# High-Level_PCB_v3_0.net
KiCad netlist of a schematic drawn in EAGLE
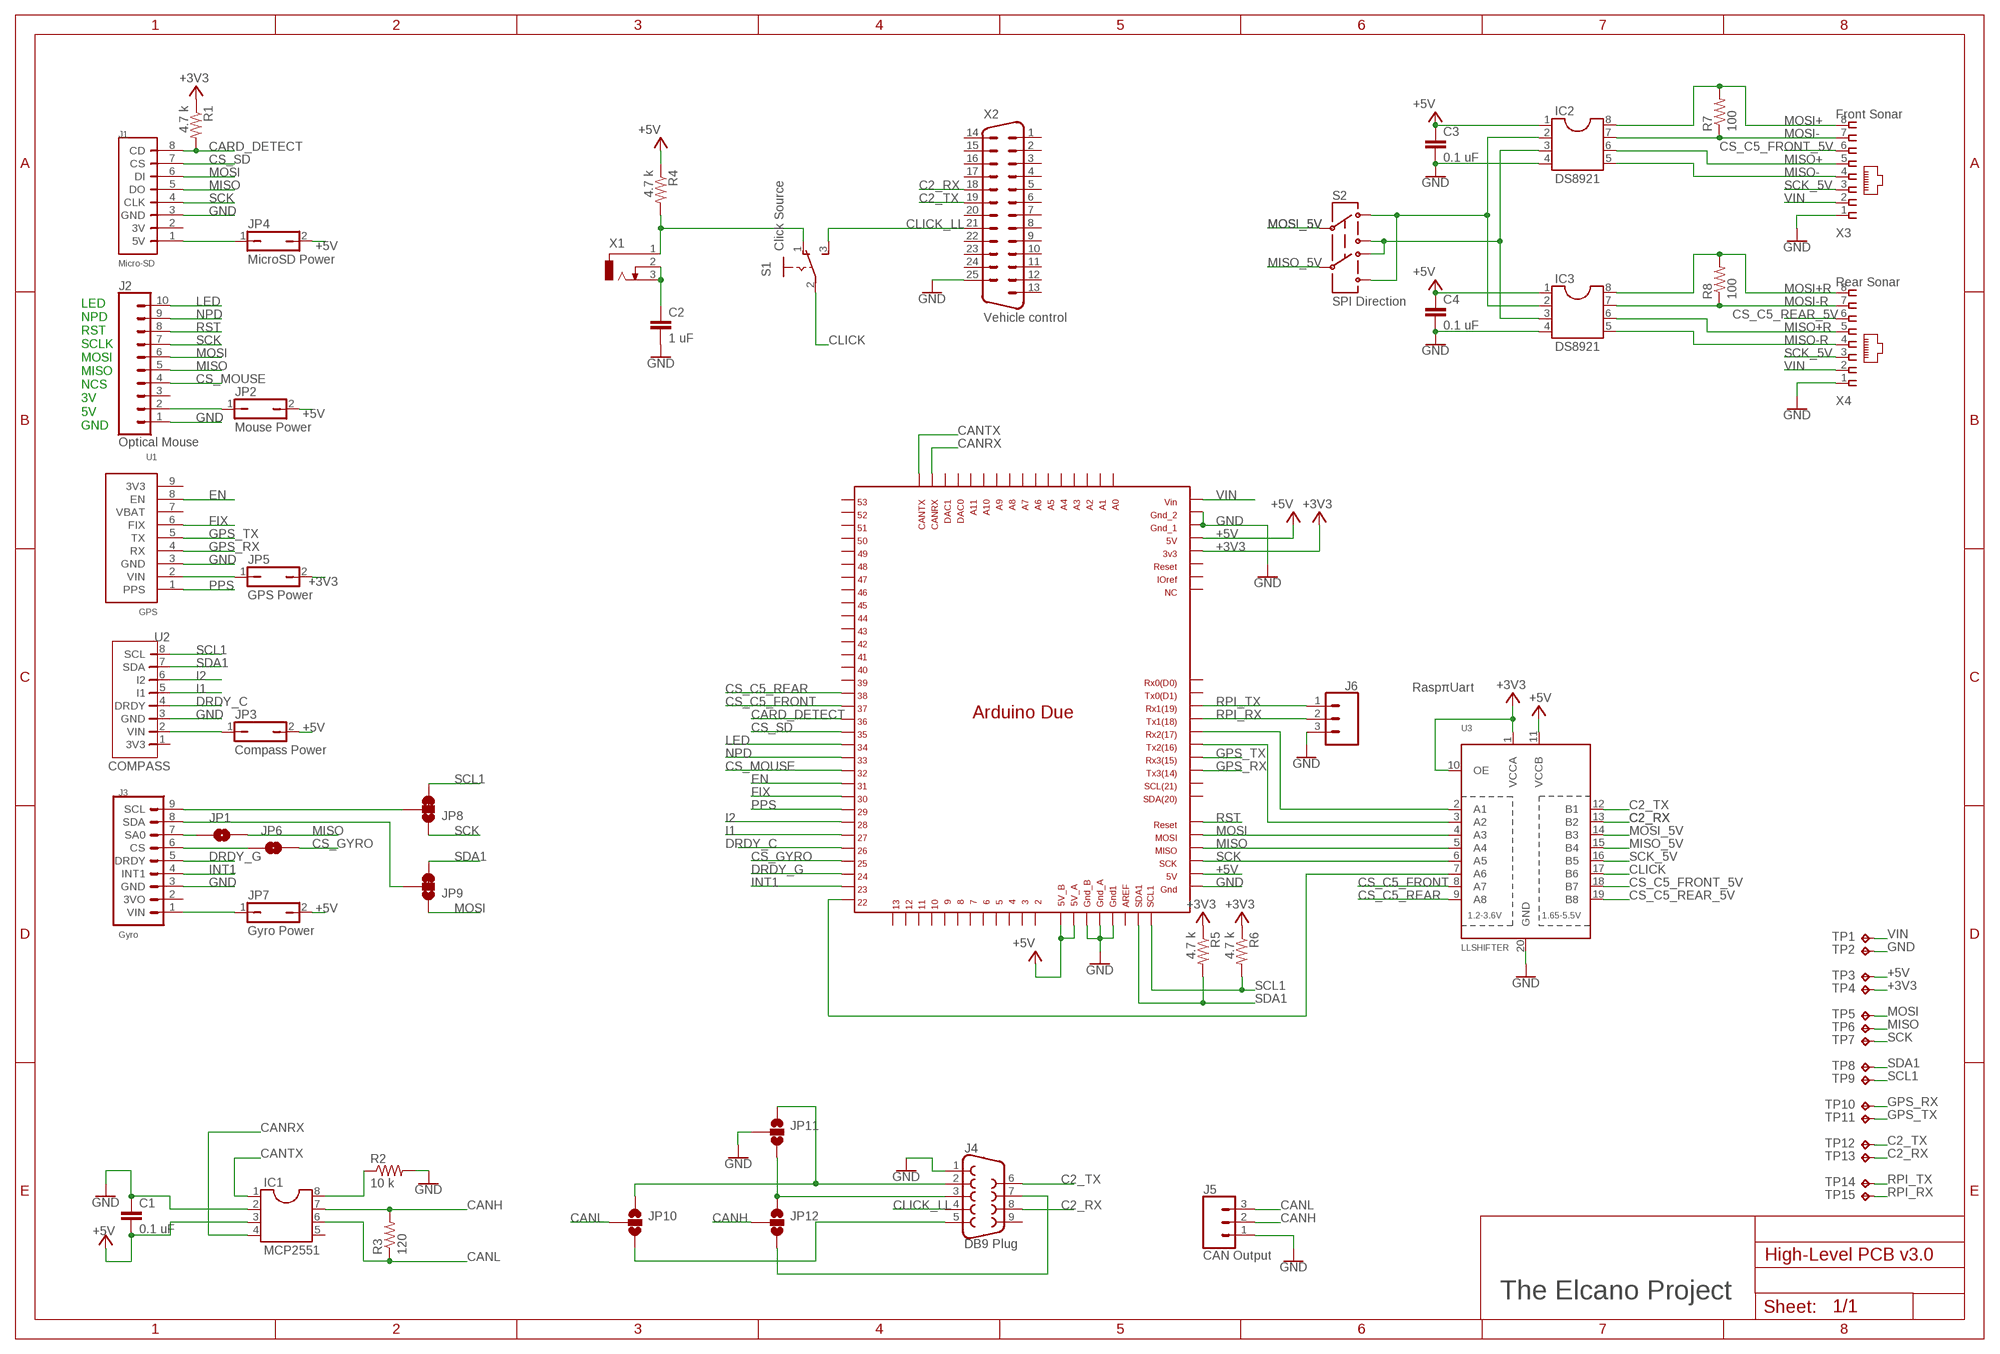
[diagram p0: schematic, sheet 1]

(export (version "E")
  (design (tool "Eeschema 10.0.6"))
  (components
    (comp (ref "C1")
      (value "0.1 uF")
      (footprint "eagle-import:C2.5-5")
      (libsource (lib "eagle-import") (part "C2.5/5"))
    )
    (comp (ref "C2")
      (value "1 uF")
      (footprint "eagle-import:C2.5-5")
      (libsource (lib "eagle-import") (part "C2.5/5"))
    )
    (comp (ref "C3")
      (value "0.1 uF")
      (footprint "eagle-import:C2.5-5")
      (libsource (lib "eagle-import") (part "C2.5/5"))
    )
    (comp (ref "C4")
      (value "0.1 uF")
      (footprint "eagle-import:C2.5-5")
      (libsource (lib "eagle-import") (part "C2.5/5"))
    )
    (comp (ref "IC1")
      (value "MCP2551")
      (footprint "eagle-import:DIL08")
      (libsource (lib "eagle-import") (part "DIL8"))
    )
    (comp (ref "IC2")
      (value "DS8921")
      (footprint "eagle-import:DIL08")
      (libsource (lib "eagle-import") (part "DIL8"))
    )
    (comp (ref "IC3")
      (value "DS8921")
      (footprint "eagle-import:DIL08")
      (libsource (lib "eagle-import") (part "DIL8"))
    )
    (comp (ref "J1")
      (value "Micro-SD")
      (footprint "eagle-import:ELSDCARD")
      (libsource (lib "eagle-import") (part "MINI_SD"))
    )
    (comp (ref "J2")
      (value "Optical Mouse")
      (footprint "eagle-import:1X10")
      (libsource (lib "eagle-import") (part "CONN_10{dblquote}"))
    )
    (comp (ref "J3")
      (value "Gyro")
      (footprint "eagle-import:ELGYRO")
      (libsource (lib "eagle-import") (part "ELGYRO_L3GD20H"))
    )
    (comp (ref "J4")
      (value "DB9 Plug")
      (footprint "eagle-import:DB9_MALE")
      (fields (field (name "SPICEPREFIX") "X"))
      (libsource (lib "eagle-import") (part "DB9MALE"))
    )
    (comp (ref "J5")
      (value "CAN Output")
      (footprint "eagle-import:SCREWTERMINAL-5MM-3")
      (libsource (lib "eagle-import") (part "CONN_03-SCREW-5MM"))
    )
    (comp (ref "J6")
      (value "RaspπUart")
      (footprint "eagle-import:1X03")
      (libsource (lib "eagle-import") (part "TXRX_2RSPPI"))
    )
    (comp (ref "JP1")
      (value "JUMPER-SMT_2_NO_SILK")
      (footprint "eagle-import:SMT-JUMPER_2_NO_SILK")
      (libsource (lib "eagle-import") (part "JUMPER-SMT_2_NO_SILK"))
    )
    (comp (ref "JP2")
      (value "Mouse Power")
      (footprint "eagle-import:JP1")
      (libsource (lib "eagle-import") (part "JP1Q"))
    )
    (comp (ref "JP3")
      (value "Compass Power")
      (footprint "eagle-import:JP1")
      (libsource (lib "eagle-import") (part "JP1Q"))
    )
    (comp (ref "JP4")
      (value "MicroSD Power")
      (footprint "eagle-import:JP1")
      (libsource (lib "eagle-import") (part "JP1Q"))
    )
    (comp (ref "JP5")
      (value "GPS Power")
      (footprint "eagle-import:JP1")
      (libsource (lib "eagle-import") (part "JP1Q"))
    )
    (comp (ref "JP6")
      (value "JUMPER-SMT_2_NO_SILK")
      (footprint "eagle-import:SMT-JUMPER_2_NO_SILK")
      (libsource (lib "eagle-import") (part "JUMPER-SMT_2_NO_SILK"))
    )
    (comp (ref "JP7")
      (value "Gyro Power")
      (footprint "eagle-import:JP1")
      (libsource (lib "eagle-import") (part "JP1Q"))
    )
    (comp (ref "JP8")
      (value "JUMPER-SMT_3_1-NC_TRACE_SILK")
      (footprint "eagle-import:SMT-JUMPER_3_1-NC_TRACE_SILK")
      (libsource (lib "eagle-import") (part "JUMPER-SMT_3_1-NC_TRACE_SILK"))
    )
    (comp (ref "JP9")
      (value "JUMPER-SMT_3_1-NC_TRACE_SILK")
      (footprint "eagle-import:SMT-JUMPER_3_1-NC_TRACE_SILK")
      (libsource (lib "eagle-import") (part "JUMPER-SMT_3_1-NC_TRACE_SILK"))
    )
    (comp (ref "JP10")
      (value "JUMPER-SMT_3_NO_SILK")
      (footprint "eagle-import:SMT-JUMPER_3_NO_SILK")
      (libsource (lib "eagle-import") (part "JUMPER-SMT_3_NO_SILK"))
    )
    (comp (ref "JP11")
      (value "JUMPER-SMT_3_NO_SILK")
      (footprint "eagle-import:SMT-JUMPER_3_NO_SILK")
      (libsource (lib "eagle-import") (part "JUMPER-SMT_3_NO_SILK"))
    )
    (comp (ref "JP12")
      (value "JUMPER-SMT_3_NO_SILK")
      (footprint "eagle-import:SMT-JUMPER_3_NO_SILK")
      (libsource (lib "eagle-import") (part "JUMPER-SMT_3_NO_SILK"))
    )
    (comp (ref "MCU1")
      (value "DUE(NORMAL)")
      (footprint "eagle-import:DUE(NORMAL)")
      (libsource (lib "eagle-import") (part "DUE(NORMAL)"))
    )
    (comp (ref "R1")
      (value "4.7 k")
      (footprint "eagle-import:0204_7")
      (libsource (lib "eagle-import") (part "resistor_348_R-US_0204/7"))
    )
    (comp (ref "R2")
      (value "10 k")
      (footprint "eagle-import:0204_7")
      (libsource (lib "eagle-import") (part "R-US_0204/7"))
    )
    (comp (ref "R3")
      (value "120")
      (footprint "eagle-import:0204_7")
      (libsource (lib "eagle-import") (part "R-US_0204/7"))
    )
    (comp (ref "R4")
      (value "4.7 k")
      (footprint "eagle-import:0204_7")
      (libsource (lib "eagle-import") (part "resistor_348_R-US_0204/7"))
    )
    (comp (ref "R5")
      (value "4.7 k")
      (footprint "eagle-import:0204_7")
      (libsource (lib "eagle-import") (part "resistor_348_R-US_0204/7"))
    )
    (comp (ref "R6")
      (value "4.7 k")
      (footprint "eagle-import:0204_7")
      (libsource (lib "eagle-import") (part "resistor_348_R-US_0204/7"))
    )
    (comp (ref "R7")
      (value "100")
      (footprint "eagle-import:0204_7")
      (libsource (lib "eagle-import") (part "R-US_0204/7"))
    )
    (comp (ref "R8")
      (value "100")
      (footprint "eagle-import:0204_7")
      (libsource (lib "eagle-import") (part "R-US_0204/7"))
    )
    (comp (ref "S1")
      (value "Click Source")
      (footprint "eagle-import:SP_ELSWITCH")
      (libsource (lib "eagle-import") (part "ELSWITCHSP"))
    )
    (comp (ref "S2")
      (value "SPI Direction")
      (footprint "eagle-import:DPDT")
      (libsource (lib "eagle-import") (part "DPDT"))
    )
    (comp (ref "TP1")
      (value "TPPAD1-17")
      (footprint "eagle-import:P1-17")
      (libsource (lib "eagle-import") (part "TPPAD1-17"))
    )
    (comp (ref "TP2")
      (value "TPPAD1-17")
      (footprint "eagle-import:P1-17")
      (libsource (lib "eagle-import") (part "TPPAD1-17"))
    )
    (comp (ref "TP3")
      (value "TPPAD1-17")
      (footprint "eagle-import:P1-17")
      (libsource (lib "eagle-import") (part "TPPAD1-17"))
    )
    (comp (ref "TP4")
      (value "TPPAD1-17")
      (footprint "eagle-import:P1-17")
      (libsource (lib "eagle-import") (part "TPPAD1-17"))
    )
    (comp (ref "TP5")
      (value "TPPAD1-17")
      (footprint "eagle-import:P1-17")
      (libsource (lib "eagle-import") (part "TPPAD1-17"))
    )
    (comp (ref "TP6")
      (value "TPPAD1-17")
      (footprint "eagle-import:P1-17")
      (libsource (lib "eagle-import") (part "TPPAD1-17"))
    )
    (comp (ref "TP7")
      (value "TPPAD1-17")
      (footprint "eagle-import:P1-17")
      (libsource (lib "eagle-import") (part "TPPAD1-17"))
    )
    (comp (ref "TP8")
      (value "TPPAD1-17")
      (footprint "eagle-import:P1-17")
      (libsource (lib "eagle-import") (part "TPPAD1-17"))
    )
    (comp (ref "TP9")
      (value "TPPAD1-17")
      (footprint "eagle-import:P1-17")
      (libsource (lib "eagle-import") (part "TPPAD1-17"))
    )
    (comp (ref "TP10")
      (value "TPPAD1-17")
      (footprint "eagle-import:P1-17")
      (libsource (lib "eagle-import") (part "TPPAD1-17"))
    )
    (comp (ref "TP11")
      (value "TPPAD1-17")
      (footprint "eagle-import:P1-17")
      (libsource (lib "eagle-import") (part "TPPAD1-17"))
    )
    (comp (ref "TP12")
      (value "TPPAD1-17")
      (footprint "eagle-import:P1-17")
      (libsource (lib "eagle-import") (part "TPPAD1-17"))
    )
    (comp (ref "TP13")
      (value "TPPAD1-17")
      (footprint "eagle-import:P1-17")
      (libsource (lib "eagle-import") (part "TPPAD1-17"))
    )
    (comp (ref "TP14")
      (value "TPPAD1-17")
      (footprint "eagle-import:P1-17")
      (libsource (lib "eagle-import") (part "TPPAD1-17"))
    )
    (comp (ref "TP15")
      (value "TPPAD1-17")
      (footprint "eagle-import:P1-17")
      (libsource (lib "eagle-import") (part "TPPAD1-17"))
    )
    (comp (ref "U1")
      (value "GPS")
      (footprint "eagle-import:ELGPS")
      (libsource (lib "eagle-import") (part "ELGPS"))
    )
    (comp (ref "U2")
      (value "COMPASS")
      (footprint "eagle-import:ELCOMPASS")
      (libsource (lib "eagle-import") (part "ELCOMPASS"))
    )
    (comp (ref "U3")
      (value "LLSHIFTER")
      (footprint "eagle-import:ELSHIFTER")
      (libsource (lib "eagle-import") (part "ELSHIFTER"))
    )
    (comp (ref "X1")
      (value "2.5MMJACK")
      (footprint "eagle-import:2.5MMJACK")
      (libsource (lib "eagle-import") (part "2.5MMJACK"))
    )
    (comp (ref "X2")
      (value "Vehicle control")
      (footprint "eagle-import:M25H")
      (libsource (lib "eagle-import") (part "M25H"))
    )
    (comp (ref "X3")
      (value "Front Sonar")
      (footprint "eagle-import:RJ45-NO-SHIELD")
      (fields (field (name "MF") "TYCO ELECTRONICS") (field (name "MPN") "RJ45-8L-B"))
      (libsource (lib "eagle-import") (part "RJ45-8L-B"))
    )
    (comp (ref "X4")
      (value "Rear Sonar")
      (footprint "eagle-import:RJ45-NO-SHIELD")
      (fields (field (name "MF") "TYCO ELECTRONICS") (field (name "MPN") "RJ45-8L-B"))
      (libsource (lib "eagle-import") (part "RJ45-8L-B"))
    )
  )
  (nets
    (net (code "1") (name "+3V3") (class "Default")
      (node (ref "JP5") (pin "2") (pinfunction "2_2") (pintype "passive"))
      (node (ref "MCU1") (pin "3V3") (pinfunction "3V3_3V3") (pintype "bidirectional"))
      (node (ref "R1") (pin "1") (pinfunction "1_1") (pintype "passive"))
      (node (ref "R5") (pin "1") (pinfunction "1_1") (pintype "passive"))
      (node (ref "R6") (pin "1") (pinfunction "1_1") (pintype "passive"))
      (node (ref "TP4") (pin "TP") (pinfunction "TP_TP") (pintype "input"))
      (node (ref "U3") (pin "1") (pinfunction "VCCA_1") (pintype "power_in"))
      (node (ref "U3") (pin "10") (pinfunction "OE_10") (pintype "bidirectional"))
    )
    (net (code "2") (name "+5V") (class "Default")
      (node (ref "C1") (pin "2") (pinfunction "2_2") (pintype "passive"))
      (node (ref "C3") (pin "1") (pinfunction "1_1") (pintype "passive"))
      (node (ref "C4") (pin "1") (pinfunction "1_1") (pintype "passive"))
      (node (ref "IC1") (pin "3") (pinfunction "3_3") (pintype "passive"))
      (node (ref "IC2") (pin "1") (pinfunction "1_1") (pintype "passive"))
      (node (ref "IC3") (pin "1") (pinfunction "1_1") (pintype "passive"))
      (node (ref "JP2") (pin "2") (pinfunction "2_2") (pintype "passive"))
      (node (ref "JP3") (pin "2") (pinfunction "2_2") (pintype "passive"))
      (node (ref "JP4") (pin "2") (pinfunction "2_2") (pintype "passive"))
      (node (ref "JP7") (pin "2") (pinfunction "2_2") (pintype "passive"))
      (node (ref "MCU1") (pin "5V") (pinfunction "5V_5V") (pintype "bidirectional"))
      (node (ref "MCU1") (pin "5V_A") (pinfunction "5V_A_5V_A") (pintype "bidirectional"))
      (node (ref "MCU1") (pin "5V_B") (pinfunction "5V_B_5V_B") (pintype "bidirectional"))
      (node (ref "MCU1") (pin "GND_ICSP") (pinfunction "GND_ICSP_GND_ICSP") (pintype "bidirectional"))
      (node (ref "R4") (pin "1") (pinfunction "1_1") (pintype "passive"))
      (node (ref "TP3") (pin "TP") (pinfunction "TP_TP") (pintype "input"))
      (node (ref "U3") (pin "11") (pinfunction "VCCB_11") (pintype "power_in"))
    )
    (net (code "3") (name "/C2_RX") (class "Default")
      (node (ref "J4") (pin "8") (pinfunction "8_8") (pintype "passive"))
      (node (ref "TP13") (pin "TP") (pinfunction "TP_TP") (pintype "input"))
      (node (ref "U3") (pin "13") (pinfunction "B2_13") (pintype "bidirectional"))
      (node (ref "X2") (pin "18") (pinfunction "18_18") (pintype "passive"))
    )
    (net (code "4") (name "/C2_TX") (class "Default")
      (node (ref "J4") (pin "6") (pinfunction "6_6") (pintype "passive"))
      (node (ref "TP12") (pin "TP") (pinfunction "TP_TP") (pintype "input"))
      (node (ref "U3") (pin "12") (pinfunction "B1_12") (pintype "bidirectional"))
      (node (ref "X2") (pin "19") (pinfunction "19_19") (pintype "passive"))
    )
    (net (code "5") (name "/CANH") (class "Default")
      (node (ref "IC1") (pin "7") (pinfunction "7_7") (pintype "passive"))
      (node (ref "J5") (pin "2") (pinfunction "2_2") (pintype "passive"))
      (node (ref "JP12") (pin "2") (pinfunction "2_2") (pintype "passive"))
      (node (ref "R3") (pin "2") (pinfunction "2_2") (pintype "passive"))
    )
    (net (code "6") (name "/CANL") (class "Default")
      (node (ref "IC1") (pin "6") (pinfunction "6_6") (pintype "passive"))
      (node (ref "J5") (pin "3") (pinfunction "3_3") (pintype "passive"))
      (node (ref "JP10") (pin "2") (pinfunction "2_2") (pintype "passive"))
      (node (ref "R3") (pin "1") (pinfunction "1_1") (pintype "passive"))
    )
    (net (code "7") (name "/CANRX") (class "Default")
      (node (ref "IC1") (pin "4") (pinfunction "4_4") (pintype "passive"))
      (node (ref "MCU1") (pin "CANRX") (pinfunction "CANRX_CANRX") (pintype "bidirectional"))
    )
    (net (code "8") (name "/CANTX") (class "Default")
      (node (ref "IC1") (pin "1") (pinfunction "1_1") (pintype "passive"))
      (node (ref "MCU1") (pin "CANTX") (pinfunction "CANTX_CANTX") (pintype "bidirectional"))
    )
    (net (code "9") (name "/CARD_DETECT") (class "Default")
      (node (ref "J1") (pin "8") (pinfunction "CD_8") (pintype "bidirectional"))
      (node (ref "MCU1") (pin "36") (pinfunction "36_36") (pintype "bidirectional"))
      (node (ref "R1") (pin "2") (pinfunction "2_2") (pintype "passive"))
    )
    (net (code "10") (name "/CLICK") (class "Default")
      (node (ref "S1") (pin "2") (pinfunction "P_2") (pintype "passive"))
      (node (ref "U3") (pin "17") (pinfunction "B6_17") (pintype "bidirectional"))
    )
    (net (code "11") (name "/CLICK_LL") (class "Default")
      (node (ref "J4") (pin "4") (pinfunction "4_4") (pintype "passive"))
      (node (ref "S1") (pin "3") (pinfunction "S_3") (pintype "passive"))
      (node (ref "X2") (pin "21") (pinfunction "21_21") (pintype "passive"))
    )
    (net (code "12") (name "/CS_C5_FRONT") (class "Default")
      (node (ref "MCU1") (pin "37") (pinfunction "37_37") (pintype "bidirectional"))
      (node (ref "U3") (pin "8") (pinfunction "A7_8") (pintype "bidirectional"))
    )
    (net (code "13") (name "/CS_C5_FRONT_5V") (class "Default")
      (node (ref "U3") (pin "18") (pinfunction "B7_18") (pintype "bidirectional"))
      (node (ref "X3") (pin "6") (pinfunction "6_6") (pintype "passive"))
    )
    (net (code "14") (name "/CS_C5_REAR") (class "Default")
      (node (ref "MCU1") (pin "38") (pinfunction "38_38") (pintype "bidirectional"))
      (node (ref "U3") (pin "9") (pinfunction "A8_9") (pintype "bidirectional"))
    )
    (net (code "15") (name "/CS_C5_REAR_5V") (class "Default")
      (node (ref "U3") (pin "19") (pinfunction "B8_19") (pintype "bidirectional"))
      (node (ref "X4") (pin "6") (pinfunction "6_6") (pintype "passive"))
    )
    (net (code "16") (name "/CS_GYRO") (class "Default")
      (node (ref "JP6") (pin "2") (pinfunction "2_2") (pintype "passive"))
      (node (ref "MCU1") (pin "25") (pinfunction "25_25") (pintype "bidirectional"))
    )
    (net (code "17") (name "/CS_MOUSE") (class "Default")
      (node (ref "J2") (pin "4") (pinfunction "4_4") (pintype "passive"))
      (node (ref "MCU1") (pin "32") (pinfunction "32_32") (pintype "bidirectional"))
    )
    (net (code "18") (name "/CS_SD") (class "Default")
      (node (ref "J1") (pin "7") (pinfunction "CS_7") (pintype "bidirectional"))
      (node (ref "MCU1") (pin "35") (pinfunction "35_35") (pintype "bidirectional"))
    )
    (net (code "19") (name "/DRDY_C") (class "Default")
      (node (ref "MCU1") (pin "26") (pinfunction "26_26") (pintype "bidirectional"))
      (node (ref "U2") (pin "4") (pinfunction "DRDY_4") (pintype "bidirectional"))
    )
    (net (code "20") (name "/DRDY_G") (class "Default")
      (node (ref "J3") (pin "5") (pinfunction "DRDY_5") (pintype "passive"))
      (node (ref "MCU1") (pin "24") (pinfunction "24_24") (pintype "bidirectional"))
    )
    (net (code "21") (name "/EN") (class "Default")
      (node (ref "MCU1") (pin "31") (pinfunction "31_31") (pintype "bidirectional"))
      (node (ref "U1") (pin "8") (pinfunction "EN_8") (pintype "bidirectional"))
    )
    (net (code "22") (name "/FIX") (class "Default")
      (node (ref "MCU1") (pin "30") (pinfunction "30_30") (pintype "bidirectional"))
      (node (ref "U1") (pin "6") (pinfunction "FIX_6") (pintype "bidirectional"))
    )
    (net (code "23") (name "/GPS_RX") (class "Default")
      (node (ref "MCU1") (pin "TX3") (pinfunction "TX3_TX3") (pintype "bidirectional"))
      (node (ref "TP10") (pin "TP") (pinfunction "TP_TP") (pintype "input"))
      (node (ref "U1") (pin "4") (pinfunction "RX_4") (pintype "input"))
    )
    (net (code "24") (name "/GPS_TX") (class "Default")
      (node (ref "MCU1") (pin "RX3") (pinfunction "RX3_RX3") (pintype "bidirectional"))
      (node (ref "TP11") (pin "TP") (pinfunction "TP_TP") (pintype "input"))
      (node (ref "U1") (pin "5") (pinfunction "TX_5") (pintype "output"))
    )
    (net (code "25") (name "/I1") (class "Default")
      (node (ref "MCU1") (pin "27") (pinfunction "27_27") (pintype "bidirectional"))
      (node (ref "U2") (pin "5") (pinfunction "I1_5") (pintype "bidirectional"))
    )
    (net (code "26") (name "/I2") (class "Default")
      (node (ref "MCU1") (pin "28") (pinfunction "28_28") (pintype "bidirectional"))
      (node (ref "U2") (pin "6") (pinfunction "I2_6") (pintype "bidirectional"))
    )
    (net (code "27") (name "/INT1") (class "Default")
      (node (ref "J3") (pin "4") (pinfunction "INT1_4") (pintype "passive"))
      (node (ref "MCU1") (pin "23") (pinfunction "23_23") (pintype "bidirectional"))
    )
    (net (code "28") (name "/LED") (class "Default")
      (node (ref "J2") (pin "10") (pinfunction "10_10") (pintype "passive"))
      (node (ref "MCU1") (pin "34") (pinfunction "34_34") (pintype "bidirectional"))
    )
    (net (code "29") (name "/MISO") (class "Default")
      (node (ref "J1") (pin "5") (pinfunction "DO_5") (pintype "bidirectional"))
      (node (ref "J2") (pin "5") (pinfunction "5_5") (pintype "passive"))
      (node (ref "JP1") (pin "2") (pinfunction "2_2") (pintype "passive"))
      (node (ref "MCU1") (pin "MISO_ICSP") (pinfunction "MISO_ICSP_MISO_ICSP") (pintype "bidirectional"))
      (node (ref "TP6") (pin "TP") (pinfunction "TP_TP") (pintype "input"))
      (node (ref "U3") (pin "5") (pinfunction "A4_5") (pintype "bidirectional"))
    )
    (net (code "30") (name "/MISO+") (class "Default")
      (node (ref "IC2") (pin "6") (pinfunction "6_6") (pintype "passive"))
      (node (ref "X3") (pin "5") (pinfunction "5_5") (pintype "passive"))
    )
    (net (code "31") (name "/MISO+R") (class "Default")
      (node (ref "IC3") (pin "6") (pinfunction "6_6") (pintype "passive"))
      (node (ref "X4") (pin "5") (pinfunction "5_5") (pintype "passive"))
    )
    (net (code "32") (name "/MISO-") (class "Default")
      (node (ref "IC2") (pin "5") (pinfunction "5_5") (pintype "passive"))
      (node (ref "X3") (pin "4") (pinfunction "4_4") (pintype "passive"))
    )
    (net (code "33") (name "/MISO-R") (class "Default")
      (node (ref "IC3") (pin "5") (pinfunction "5_5") (pintype "passive"))
      (node (ref "X4") (pin "4") (pinfunction "4_4") (pintype "passive"))
    )
    (net (code "34") (name "/MISO_5V") (class "Default")
      (node (ref "S2") (pin "5") (pinfunction "5_5") (pintype "bidirectional"))
      (node (ref "U3") (pin "15") (pinfunction "B4_15") (pintype "bidirectional"))
    )
    (net (code "35") (name "/MOSI") (class "Default")
      (node (ref "J1") (pin "6") (pinfunction "DI_6") (pintype "bidirectional"))
      (node (ref "J2") (pin "6") (pinfunction "6_6") (pintype "passive"))
      (node (ref "JP9") (pin "1") (pinfunction "1_1") (pintype "passive"))
      (node (ref "MCU1") (pin "MOSI_ICSP") (pinfunction "MOSI_ICSP_MOSI_ICSP") (pintype "bidirectional"))
      (node (ref "TP5") (pin "TP") (pinfunction "TP_TP") (pintype "input"))
      (node (ref "U3") (pin "4") (pinfunction "A3_4") (pintype "bidirectional"))
    )
    (net (code "36") (name "/MOSI+") (class "Default")
      (node (ref "IC2") (pin "8") (pinfunction "8_8") (pintype "passive"))
      (node (ref "R7") (pin "2") (pinfunction "2_2") (pintype "passive"))
      (node (ref "X3") (pin "8") (pinfunction "8_8") (pintype "passive"))
    )
    (net (code "37") (name "/MOSI+R") (class "Default")
      (node (ref "IC3") (pin "8") (pinfunction "8_8") (pintype "passive"))
      (node (ref "R8") (pin "2") (pinfunction "2_2") (pintype "passive"))
      (node (ref "X4") (pin "8") (pinfunction "8_8") (pintype "passive"))
    )
    (net (code "38") (name "/MOSI-") (class "Default")
      (node (ref "IC2") (pin "7") (pinfunction "7_7") (pintype "passive"))
      (node (ref "R7") (pin "1") (pinfunction "1_1") (pintype "passive"))
      (node (ref "X3") (pin "7") (pinfunction "7_7") (pintype "passive"))
    )
    (net (code "39") (name "/MOSI-R") (class "Default")
      (node (ref "IC3") (pin "7") (pinfunction "7_7") (pintype "passive"))
      (node (ref "R8") (pin "1") (pinfunction "1_1") (pintype "passive"))
      (node (ref "X4") (pin "7") (pinfunction "7_7") (pintype "passive"))
    )
    (net (code "40") (name "/MOSI_5V") (class "Default")
      (node (ref "S2") (pin "2") (pinfunction "2_2") (pintype "bidirectional"))
      (node (ref "U3") (pin "14") (pinfunction "B3_14") (pintype "bidirectional"))
    )
    (net (code "41") (name "/NPD") (class "Default")
      (node (ref "J2") (pin "9") (pinfunction "9_9") (pintype "passive"))
      (node (ref "MCU1") (pin "33") (pinfunction "33_33") (pintype "bidirectional"))
    )
    (net (code "42") (name "/PPS") (class "Default")
      (node (ref "MCU1") (pin "29") (pinfunction "29_29") (pintype "bidirectional"))
      (node (ref "U1") (pin "1") (pinfunction "PPS_1") (pintype "bidirectional"))
    )
    (net (code "43") (name "/RPI_RX") (class "Default")
      (node (ref "J6") (pin "2") (pinfunction "1_2") (pintype "passive"))
      (node (ref "MCU1") (pin "TX1") (pinfunction "TX1_TX1") (pintype "bidirectional"))
      (node (ref "TP15") (pin "TP") (pinfunction "TP_TP") (pintype "input"))
    )
    (net (code "44") (name "/RPI_TX") (class "Default")
      (node (ref "J6") (pin "1") (pinfunction "2_1") (pintype "passive"))
      (node (ref "MCU1") (pin "RX1") (pinfunction "RX1_RX1") (pintype "bidirectional"))
      (node (ref "TP14") (pin "TP") (pinfunction "TP_TP") (pintype "input"))
    )
    (net (code "45") (name "/RST") (class "Default")
      (node (ref "J2") (pin "8") (pinfunction "8_8") (pintype "passive"))
      (node (ref "MCU1") (pin "RESET_ICSP") (pinfunction "RESET_ICSP_RESET_ICSP") (pintype "bidirectional"))
    )
    (net (code "46") (name "/SCK") (class "Default")
      (node (ref "J1") (pin "4") (pinfunction "CLK_4") (pintype "bidirectional"))
      (node (ref "J2") (pin "7") (pinfunction "7_7") (pintype "passive"))
      (node (ref "JP8") (pin "1") (pinfunction "1_1") (pintype "passive"))
      (node (ref "MCU1") (pin "SCK_ICSP") (pinfunction "SCK_ICSP_SCK_ICSP") (pintype "bidirectional"))
      (node (ref "TP7") (pin "TP") (pinfunction "TP_TP") (pintype "input"))
      (node (ref "U3") (pin "6") (pinfunction "A5_6") (pintype "bidirectional"))
    )
    (net (code "47") (name "/SCK_5V") (class "Default")
      (node (ref "U3") (pin "16") (pinfunction "B5_16") (pintype "bidirectional"))
      (node (ref "X3") (pin "3") (pinfunction "3_3") (pintype "passive"))
      (node (ref "X4") (pin "3") (pinfunction "3_3") (pintype "passive"))
    )
    (net (code "48") (name "/SCL1") (class "Default")
      (node (ref "JP8") (pin "3") (pinfunction "3_3") (pintype "passive"))
      (node (ref "MCU1") (pin "SCL1") (pinfunction "SCL1_SCL1") (pintype "bidirectional"))
      (node (ref "R6") (pin "2") (pinfunction "2_2") (pintype "passive"))
      (node (ref "TP9") (pin "TP") (pinfunction "TP_TP") (pintype "input"))
      (node (ref "U2") (pin "8") (pinfunction "SCL_8") (pintype "bidirectional"))
    )
    (net (code "49") (name "/SDA1") (class "Default")
      (node (ref "JP9") (pin "3") (pinfunction "3_3") (pintype "passive"))
      (node (ref "MCU1") (pin "SDA1") (pinfunction "SDA1_SDA1") (pintype "bidirectional"))
      (node (ref "R5") (pin "2") (pinfunction "2_2") (pintype "passive"))
      (node (ref "TP8") (pin "TP") (pinfunction "TP_TP") (pintype "input"))
      (node (ref "U2") (pin "7") (pinfunction "SDA_7") (pintype "bidirectional"))
    )
    (net (code "50") (name "/VIN") (class "Default")
      (node (ref "MCU1") (pin "VIN") (pinfunction "VIN_VIN") (pintype "bidirectional"))
      (node (ref "TP1") (pin "TP") (pinfunction "TP_TP") (pintype "input"))
      (node (ref "X3") (pin "2") (pinfunction "2_2") (pintype "passive"))
      (node (ref "X4") (pin "2") (pinfunction "2_2") (pintype "passive"))
    )
    (net (code "51") (name "GND") (class "Default")
      (node (ref "C1") (pin "1") (pinfunction "1_1") (pintype "passive"))
      (node (ref "C2") (pin "2") (pinfunction "2_2") (pintype "passive"))
      (node (ref "C3") (pin "2") (pinfunction "2_2") (pintype "passive"))
      (node (ref "C4") (pin "2") (pinfunction "2_2") (pintype "passive"))
      (node (ref "IC1") (pin "2") (pinfunction "2_2") (pintype "passive"))
      (node (ref "IC2") (pin "4") (pinfunction "4_4") (pintype "passive"))
      (node (ref "IC3") (pin "4") (pinfunction "4_4") (pintype "passive"))
      (node (ref "J1") (pin "3") (pinfunction "GND_3") (pintype "bidirectional"))
      (node (ref "J2") (pin "1") (pinfunction "1_1") (pintype "passive"))
      (node (ref "J3") (pin "3") (pinfunction "GND_3") (pintype "passive"))
      (node (ref "J4") (pin "1") (pinfunction "1_1") (pintype "passive"))
      (node (ref "J5") (pin "1") (pinfunction "1_1") (pintype "passive"))
      (node (ref "J6") (pin "3") (pinfunction "3_3") (pintype "passive"))
      (node (ref "JP11") (pin "2") (pinfunction "2_2") (pintype "passive"))
      (node (ref "MCU1") (pin "5V_ICSP") (pinfunction "5V_ICSP_5V_ICSP") (pintype "bidirectional"))
      (node (ref "MCU1") (pin "GND1") (pinfunction "GND1_GND1") (pintype "bidirectional"))
      (node (ref "MCU1") (pin "GND_1") (pinfunction "GND_1_GND_1") (pintype "bidirectional"))
      (node (ref "MCU1") (pin "GND_2") (pinfunction "GND_2_GND_2") (pintype "bidirectional"))
      (node (ref "MCU1") (pin "GND_A") (pinfunction "GND_A_GND_A") (pintype "bidirectional"))
      (node (ref "MCU1") (pin "GND_B") (pinfunction "GND_B_GND_B") (pintype "bidirectional"))
      (node (ref "R2") (pin "2") (pinfunction "2_2") (pintype "passive"))
      (node (ref "TP2") (pin "TP") (pinfunction "TP_TP") (pintype "input"))
      (node (ref "U1") (pin "3") (pinfunction "GND_3") (pintype "power_in"))
      (node (ref "U2") (pin "3") (pinfunction "GND_3") (pintype "power_in"))
      (node (ref "U3") (pin "20") (pinfunction "GND_20") (pintype "power_in"))
      (node (ref "X2") (pin "25") (pinfunction "25_25") (pintype "passive"))
      (node (ref "X3") (pin "1") (pinfunction "1_1") (pintype "passive"))
      (node (ref "X4") (pin "1") (pinfunction "1_1") (pintype "passive"))
    )
    (net (code "52") (name "Net-(C2-Pad1)") (class "Default")
      (node (ref "C2") (pin "1") (pinfunction "1_1") (pintype "passive"))
      (node (ref "X1") (pin "2") (pinfunction "2_2") (pintype "passive"))
      (node (ref "X1") (pin "3") (pinfunction "3_3") (pintype "passive"))
    )
    (net (code "53") (name "Net-(IC1-Pad8)") (class "Default")
      (node (ref "IC1") (pin "8") (pinfunction "8_8") (pintype "passive"))
      (node (ref "R2") (pin "1") (pinfunction "1_1") (pintype "passive"))
    )
    (net (code "54") (name "Net-(IC2-Pad2)") (class "Default")
      (node (ref "IC2") (pin "2") (pinfunction "2_2") (pintype "passive"))
      (node (ref "IC3") (pin "2") (pinfunction "2_2") (pintype "passive"))
      (node (ref "S2") (pin "1") (pinfunction "1_1") (pintype "bidirectional"))
      (node (ref "S2") (pin "6") (pinfunction "6_6") (pintype "bidirectional"))
    )
    (net (code "55") (name "Net-(IC2-Pad3)") (class "Default")
      (node (ref "IC2") (pin "3") (pinfunction "3_3") (pintype "passive"))
      (node (ref "IC3") (pin "3") (pinfunction "3_3") (pintype "passive"))
      (node (ref "S2") (pin "3") (pinfunction "3_3") (pintype "bidirectional"))
      (node (ref "S2") (pin "4") (pinfunction "4_4") (pintype "bidirectional"))
    )
    (net (code "56") (name "Net-(J1-5V)") (class "Default")
      (node (ref "J1") (pin "1") (pinfunction "5V_1") (pintype "bidirectional"))
      (node (ref "JP4") (pin "1") (pinfunction "1_1") (pintype "passive"))
    )
    (net (code "57") (name "Net-(J2-Pad2)") (class "Default")
      (node (ref "J2") (pin "2") (pinfunction "2_2") (pintype "passive"))
      (node (ref "JP2") (pin "1") (pinfunction "1_1") (pintype "passive"))
    )
    (net (code "58") (name "Net-(J3-CS)") (class "Default")
      (node (ref "J3") (pin "6") (pinfunction "CS_6") (pintype "passive"))
      (node (ref "JP6") (pin "1") (pinfunction "1_1") (pintype "passive"))
    )
    (net (code "59") (name "Net-(J3-SA0)") (class "Default")
      (node (ref "J3") (pin "7") (pinfunction "SA0_7") (pintype "passive"))
      (node (ref "JP1") (pin "1") (pinfunction "1_1") (pintype "passive"))
    )
    (net (code "60") (name "Net-(J3-SCL)") (class "Default")
      (node (ref "J3") (pin "9") (pinfunction "SCL_9") (pintype "passive"))
      (node (ref "JP8") (pin "2") (pinfunction "2_2") (pintype "passive"))
    )
    (net (code "61") (name "Net-(J3-SDA)") (class "Default")
      (node (ref "J3") (pin "8") (pinfunction "SDA_8") (pintype "passive"))
      (node (ref "JP9") (pin "2") (pinfunction "2_2") (pintype "passive"))
    )
    (net (code "62") (name "Net-(J3-VIN)") (class "Default")
      (node (ref "J3") (pin "1") (pinfunction "VIN_1") (pintype "passive"))
      (node (ref "JP7") (pin "1") (pinfunction "1_1") (pintype "passive"))
    )
    (net (code "63") (name "Net-(J4-Pad2)") (class "Default")
      (node (ref "J4") (pin "2") (pinfunction "2_2") (pintype "passive"))
      (node (ref "JP10") (pin "1") (pinfunction "1_1") (pintype "passive"))
      (node (ref "JP11") (pin "1") (pinfunction "1_1") (pintype "passive"))
    )
    (net (code "64") (name "Net-(J4-Pad3)") (class "Default")
      (node (ref "J4") (pin "3") (pinfunction "3_3") (pintype "passive"))
      (node (ref "JP11") (pin "3") (pinfunction "3_3") (pintype "passive"))
      (node (ref "JP12") (pin "1") (pinfunction "1_1") (pintype "passive"))
    )
    (net (code "65") (name "Net-(J4-Pad5)") (class "Default")
      (node (ref "J4") (pin "5") (pinfunction "5_5") (pintype "passive"))
      (node (ref "JP10") (pin "3") (pinfunction "3_3") (pintype "passive"))
    )
    (net (code "66") (name "Net-(J4-Pad7)") (class "Default")
      (node (ref "J4") (pin "7") (pinfunction "7_7") (pintype "passive"))
      (node (ref "JP12") (pin "3") (pinfunction "3_3") (pintype "passive"))
    )
    (net (code "67") (name "Net-(S1-O)") (class "Default")
      (node (ref "R4") (pin "2") (pinfunction "2_2") (pintype "passive"))
      (node (ref "S1") (pin "1") (pinfunction "O_1") (pintype "passive"))
      (node (ref "X1") (pin "1") (pinfunction "1_1") (pintype "passive"))
    )
    (net (code "68") (name "Net-(U1-VIN)") (class "Default")
      (node (ref "JP5") (pin "1") (pinfunction "1_1") (pintype "passive"))
      (node (ref "U1") (pin "2") (pinfunction "VIN_2") (pintype "power_in"))
    )
    (net (code "69") (name "Net-(U2-VIN)") (class "Default")
      (node (ref "JP3") (pin "1") (pinfunction "1_1") (pintype "passive"))
      (node (ref "U2") (pin "2") (pinfunction "VIN_2") (pintype "power_in"))
    )
    (net (code "70") (name "Net-(U3-A1)") (class "Default")
      (node (ref "MCU1") (pin "RX2") (pinfunction "RX2_RX2") (pintype "bidirectional"))
      (node (ref "U3") (pin "2") (pinfunction "A1_2") (pintype "bidirectional"))
    )
    (net (code "71") (name "Net-(U3-A2)") (class "Default")
      (node (ref "MCU1") (pin "TX2") (pinfunction "TX2_TX2") (pintype "bidirectional"))
      (node (ref "U3") (pin "3") (pinfunction "A2_3") (pintype "bidirectional"))
    )
    (net (code "72") (name "Net-(U3-A6)") (class "Default")
      (node (ref "MCU1") (pin "22") (pinfunction "22_22") (pintype "bidirectional"))
      (node (ref "U3") (pin "7") (pinfunction "A6_7") (pintype "bidirectional"))
    )
    (net (code "73") (name "unconnected-(IC1-Pad5)") (class "Default")
      (node (ref "IC1") (pin "5") (pinfunction "5_5") (pintype "passive"))
    )
    (net (code "74") (name "unconnected-(J1-3V-Pad2)") (class "Default")
      (node (ref "J1") (pin "2") (pinfunction "3V_2") (pintype "bidirectional"))
    )
    (net (code "75") (name "unconnected-(J2-Pad3)") (class "Default")
      (node (ref "J2") (pin "3") (pinfunction "3_3") (pintype "passive"))
    )
    (net (code "76") (name "unconnected-(J3-3VO-Pad2)") (class "Default")
      (node (ref "J3") (pin "2") (pinfunction "3VO_2") (pintype "passive"))
    )
    (net (code "77") (name "unconnected-(J4-Pad9)") (class "Default")
      (node (ref "J4") (pin "9") (pinfunction "9_9") (pintype "passive"))
    )
    (net (code "78") (name "unconnected-(MCU1-Pad2)") (class "Default")
      (node (ref "MCU1") (pin "2") (pinfunction "2_2") (pintype "bidirectional"))
    )
    (net (code "79") (name "unconnected-(MCU1-Pad3)") (class "Default")
      (node (ref "MCU1") (pin "3") (pinfunction "3_3") (pintype "bidirectional"))
    )
    (net (code "80") (name "unconnected-(MCU1-Pad4)") (class "Default")
      (node (ref "MCU1") (pin "4") (pinfunction "4_4") (pintype "bidirectional"))
    )
    (net (code "81") (name "unconnected-(MCU1-Pad5)") (class "Default")
      (node (ref "MCU1") (pin "5") (pinfunction "5_5") (pintype "bidirectional"))
    )
    (net (code "82") (name "unconnected-(MCU1-Pad6)") (class "Default")
      (node (ref "MCU1") (pin "6") (pinfunction "6_6") (pintype "bidirectional"))
    )
    (net (code "83") (name "unconnected-(MCU1-Pad7)") (class "Default")
      (node (ref "MCU1") (pin "7") (pinfunction "7_7") (pintype "bidirectional"))
    )
    (net (code "84") (name "unconnected-(MCU1-Pad8)") (class "Default")
      (node (ref "MCU1") (pin "8") (pinfunction "8_8") (pintype "bidirectional"))
    )
    (net (code "85") (name "unconnected-(MCU1-Pad9)") (class "Default")
      (node (ref "MCU1") (pin "9") (pinfunction "9_9") (pintype "bidirectional"))
    )
    (net (code "86") (name "unconnected-(MCU1-Pad10)") (class "Default")
      (node (ref "MCU1") (pin "10") (pinfunction "10_10") (pintype "bidirectional"))
    )
    (net (code "87") (name "unconnected-(MCU1-Pad11)") (class "Default")
      (node (ref "MCU1") (pin "11") (pinfunction "11_11") (pintype "bidirectional"))
    )
    (net (code "88") (name "unconnected-(MCU1-Pad12)") (class "Default")
      (node (ref "MCU1") (pin "12") (pinfunction "12_12") (pintype "bidirectional"))
    )
    (net (code "89") (name "unconnected-(MCU1-Pad13)") (class "Default")
      (node (ref "MCU1") (pin "13") (pinfunction "13_13") (pintype "bidirectional"))
    )
    (net (code "90") (name "unconnected-(MCU1-Pad39)") (class "Default")
      (node (ref "MCU1") (pin "39") (pinfunction "39_39") (pintype "bidirectional"))
    )
    (net (code "91") (name "unconnected-(MCU1-Pad40)") (class "Default")
      (node (ref "MCU1") (pin "40") (pinfunction "40_40") (pintype "bidirectional"))
    )
    (net (code "92") (name "unconnected-(MCU1-Pad41)") (class "Default")
      (node (ref "MCU1") (pin "41") (pinfunction "41_41") (pintype "bidirectional"))
    )
    (net (code "93") (name "unconnected-(MCU1-Pad42)") (class "Default")
      (node (ref "MCU1") (pin "42") (pinfunction "42_42") (pintype "bidirectional"))
    )
    (net (code "94") (name "unconnected-(MCU1-Pad43)") (class "Default")
      (node (ref "MCU1") (pin "43") (pinfunction "43_43") (pintype "bidirectional"))
    )
    (net (code "95") (name "unconnected-(MCU1-Pad44)") (class "Default")
      (node (ref "MCU1") (pin "44") (pinfunction "44_44") (pintype "bidirectional"))
    )
    (net (code "96") (name "unconnected-(MCU1-Pad45)") (class "Default")
      (node (ref "MCU1") (pin "45") (pinfunction "45_45") (pintype "bidirectional"))
    )
    (net (code "97") (name "unconnected-(MCU1-Pad46)") (class "Default")
      (node (ref "MCU1") (pin "46") (pinfunction "46_46") (pintype "bidirectional"))
    )
    (net (code "98") (name "unconnected-(MCU1-Pad47)") (class "Default")
      (node (ref "MCU1") (pin "47") (pinfunction "47_47") (pintype "bidirectional"))
    )
    (net (code "99") (name "unconnected-(MCU1-Pad48)") (class "Default")
      (node (ref "MCU1") (pin "48") (pinfunction "48_48") (pintype "bidirectional"))
    )
    (net (code "100") (name "unconnected-(MCU1-Pad49)") (class "Default")
      (node (ref "MCU1") (pin "49") (pinfunction "49_49") (pintype "bidirectional"))
    )
    (net (code "101") (name "unconnected-(MCU1-Pad50)") (class "Default")
      (node (ref "MCU1") (pin "50") (pinfunction "50_50") (pintype "bidirectional"))
    )
    (net (code "102") (name "unconnected-(MCU1-Pad51)") (class "Default")
      (node (ref "MCU1") (pin "51") (pinfunction "51_51") (pintype "bidirectional"))
    )
    (net (code "103") (name "unconnected-(MCU1-Pad52)") (class "Default")
      (node (ref "MCU1") (pin "52") (pinfunction "52_52") (pintype "bidirectional"))
    )
    (net (code "104") (name "unconnected-(MCU1-Pad53)") (class "Default")
      (node (ref "MCU1") (pin "53") (pinfunction "53_53") (pintype "bidirectional"))
    )
    (net (code "105") (name "unconnected-(MCU1-PadA0)") (class "Default")
      (node (ref "MCU1") (pin "A0") (pinfunction "A0_A0") (pintype "bidirectional"))
    )
    (net (code "106") (name "unconnected-(MCU1-PadA1)") (class "Default")
      (node (ref "MCU1") (pin "A1") (pinfunction "A1_A1") (pintype "bidirectional"))
    )
    (net (code "107") (name "unconnected-(MCU1-PadA2)") (class "Default")
      (node (ref "MCU1") (pin "A2") (pinfunction "A2_A2") (pintype "bidirectional"))
    )
    (net (code "108") (name "unconnected-(MCU1-PadA3)") (class "Default")
      (node (ref "MCU1") (pin "A3") (pinfunction "A3_A3") (pintype "bidirectional"))
    )
    (net (code "109") (name "unconnected-(MCU1-PadA4)") (class "Default")
      (node (ref "MCU1") (pin "A4") (pinfunction "A4_A4") (pintype "bidirectional"))
    )
    (net (code "110") (name "unconnected-(MCU1-PadA5)") (class "Default")
      (node (ref "MCU1") (pin "A5") (pinfunction "A5_A5") (pintype "bidirectional"))
    )
    (net (code "111") (name "unconnected-(MCU1-PadA6)") (class "Default")
      (node (ref "MCU1") (pin "A6") (pinfunction "A6_A6") (pintype "bidirectional"))
    )
    (net (code "112") (name "unconnected-(MCU1-PadA7)") (class "Default")
      (node (ref "MCU1") (pin "A7") (pinfunction "A7_A7") (pintype "bidirectional"))
    )
    (net (code "113") (name "unconnected-(MCU1-PadA8)") (class "Default")
      (node (ref "MCU1") (pin "A8") (pinfunction "A8_A8") (pintype "bidirectional"))
    )
    (net (code "114") (name "unconnected-(MCU1-PadA9)") (class "Default")
      (node (ref "MCU1") (pin "A9") (pinfunction "A9_A9") (pintype "bidirectional"))
    )
    (net (code "115") (name "unconnected-(MCU1-PadA10)") (class "Default")
      (node (ref "MCU1") (pin "A10") (pinfunction "A10_A10") (pintype "bidirectional"))
    )
    (net (code "116") (name "unconnected-(MCU1-PadA11)") (class "Default")
      (node (ref "MCU1") (pin "A11") (pinfunction "A11_A11") (pintype "bidirectional"))
    )
    (net (code "117") (name "unconnected-(MCU1-PadAREF)") (class "Default")
      (node (ref "MCU1") (pin "AREF") (pinfunction "AREF_AREF") (pintype "bidirectional"))
    )
    (net (code "118") (name "unconnected-(MCU1-PadDAC0)") (class "Default")
      (node (ref "MCU1") (pin "DAC0") (pinfunction "DAC0_DAC0") (pintype "bidirectional"))
    )
    (net (code "119") (name "unconnected-(MCU1-PadDAC1)") (class "Default")
      (node (ref "MCU1") (pin "DAC1") (pinfunction "DAC1_DAC1") (pintype "bidirectional"))
    )
    (net (code "120") (name "unconnected-(MCU1-PadIOREF)") (class "Default")
      (node (ref "MCU1") (pin "IOREF") (pinfunction "IOREF_IOREF") (pintype "bidirectional"))
    )
    (net (code "121") (name "unconnected-(MCU1-PadNC)") (class "Default")
      (node (ref "MCU1") (pin "NC") (pinfunction "NC_NC") (pintype "bidirectional"))
    )
    (net (code "122") (name "unconnected-(MCU1-PadRESET)") (class "Default")
      (node (ref "MCU1") (pin "RESET") (pinfunction "RESET_RESET") (pintype "bidirectional"))
    )
    (net (code "123") (name "unconnected-(MCU1-PadRX0)") (class "Default")
      (node (ref "MCU1") (pin "RX0") (pinfunction "RX0_RX0") (pintype "bidirectional"))
    )
    (net (code "124") (name "unconnected-(MCU1-PadSCL)") (class "Default")
      (node (ref "MCU1") (pin "SCL") (pinfunction "SCL_SCL") (pintype "bidirectional"))
    )
    (net (code "125") (name "unconnected-(MCU1-PadSDA)") (class "Default")
      (node (ref "MCU1") (pin "SDA") (pinfunction "SDA_SDA") (pintype "bidirectional"))
    )
    (net (code "126") (name "unconnected-(MCU1-PadTX0)") (class "Default")
      (node (ref "MCU1") (pin "TX0") (pinfunction "TX0_TX0") (pintype "bidirectional"))
    )
    (net (code "127") (name "unconnected-(U1-3V3-Pad9)") (class "Default")
      (node (ref "U1") (pin "9") (pinfunction "3V3_9") (pintype "no_connect"))
    )
    (net (code "128") (name "unconnected-(U1-VBAT-Pad7)") (class "Default")
      (node (ref "U1") (pin "7") (pinfunction "VBAT_7") (pintype "no_connect"))
    )
    (net (code "129") (name "unconnected-(U2-3V3-Pad1)") (class "Default")
      (node (ref "U2") (pin "1") (pinfunction "3V3_1") (pintype "no_connect"))
    )
    (net (code "130") (name "unconnected-(X2-Pad1)") (class "Default")
      (node (ref "X2") (pin "1") (pinfunction "1_1") (pintype "passive"))
    )
    (net (code "131") (name "unconnected-(X2-Pad2)") (class "Default")
      (node (ref "X2") (pin "2") (pinfunction "2_2") (pintype "passive"))
    )
    (net (code "132") (name "unconnected-(X2-Pad3)") (class "Default")
      (node (ref "X2") (pin "3") (pinfunction "3_3") (pintype "passive"))
    )
    (net (code "133") (name "unconnected-(X2-Pad4)") (class "Default")
      (node (ref "X2") (pin "4") (pinfunction "4_4") (pintype "passive"))
    )
    (net (code "134") (name "unconnected-(X2-Pad5)") (class "Default")
      (node (ref "X2") (pin "5") (pinfunction "5_5") (pintype "passive"))
    )
    (net (code "135") (name "unconnected-(X2-Pad6)") (class "Default")
      (node (ref "X2") (pin "6") (pinfunction "6_6") (pintype "passive"))
    )
    (net (code "136") (name "unconnected-(X2-Pad7)") (class "Default")
      (node (ref "X2") (pin "7") (pinfunction "7_7") (pintype "passive"))
    )
    (net (code "137") (name "unconnected-(X2-Pad8)") (class "Default")
      (node (ref "X2") (pin "8") (pinfunction "8_8") (pintype "passive"))
    )
    (net (code "138") (name "unconnected-(X2-Pad9)") (class "Default")
      (node (ref "X2") (pin "9") (pinfunction "9_9") (pintype "passive"))
    )
    (net (code "139") (name "unconnected-(X2-Pad10)") (class "Default")
      (node (ref "X2") (pin "10") (pinfunction "10_10") (pintype "passive"))
    )
    (net (code "140") (name "unconnected-(X2-Pad11)") (class "Default")
      (node (ref "X2") (pin "11") (pinfunction "11_11") (pintype "passive"))
    )
    (net (code "141") (name "unconnected-(X2-Pad12)") (class "Default")
      (node (ref "X2") (pin "12") (pinfunction "12_12") (pintype "passive"))
    )
    (net (code "142") (name "unconnected-(X2-Pad13)") (class "Default")
      (node (ref "X2") (pin "13") (pinfunction "13_13") (pintype "passive"))
    )
    (net (code "143") (name "unconnected-(X2-Pad14)") (class "Default")
      (node (ref "X2") (pin "14") (pinfunction "14_14") (pintype "passive"))
    )
    (net (code "144") (name "unconnected-(X2-Pad15)") (class "Default")
      (node (ref "X2") (pin "15") (pinfunction "15_15") (pintype "passive"))
    )
    (net (code "145") (name "unconnected-(X2-Pad16)") (class "Default")
      (node (ref "X2") (pin "16") (pinfunction "16_16") (pintype "passive"))
    )
    (net (code "146") (name "unconnected-(X2-Pad17)") (class "Default")
      (node (ref "X2") (pin "17") (pinfunction "17_17") (pintype "passive"))
    )
    (net (code "147") (name "unconnected-(X2-Pad20)") (class "Default")
      (node (ref "X2") (pin "20") (pinfunction "20_20") (pintype "passive"))
    )
    (net (code "148") (name "unconnected-(X2-Pad22)") (class "Default")
      (node (ref "X2") (pin "22") (pinfunction "22_22") (pintype "passive"))
    )
    (net (code "149") (name "unconnected-(X2-Pad23)") (class "Default")
      (node (ref "X2") (pin "23") (pinfunction "23_23") (pintype "passive"))
    )
    (net (code "150") (name "unconnected-(X2-Pad24)") (class "Default")
      (node (ref "X2") (pin "24") (pinfunction "24_24") (pintype "passive"))
    )
  )
)
